# MEGA-ROS.net
KiCad netlist of a schematic drawn in EAGLE
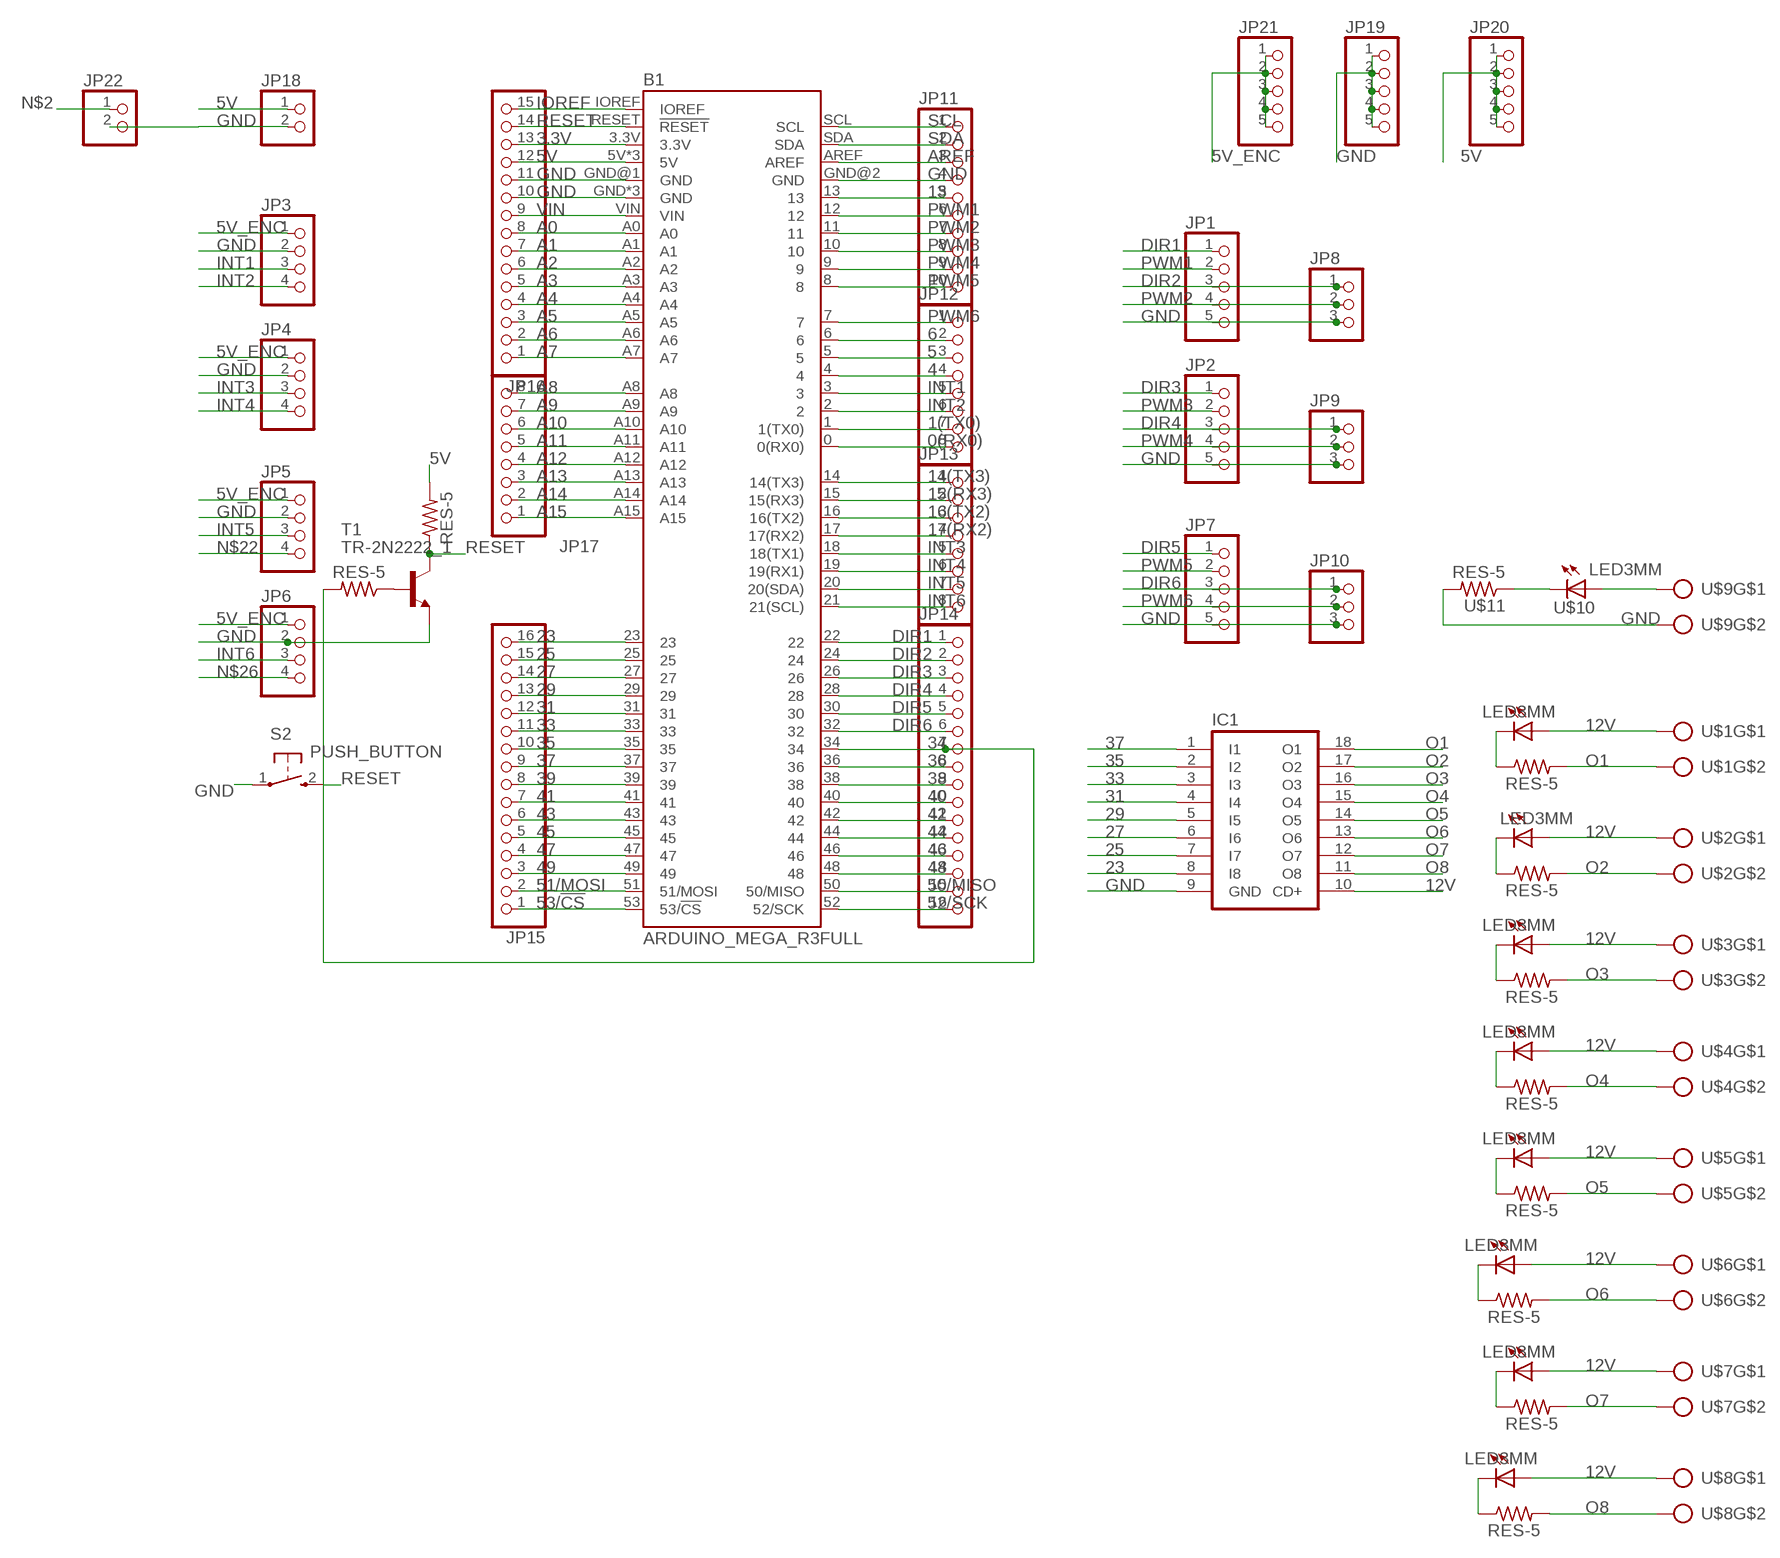
[diagram p0: schematic, sheet 1]

(export (version "E")
  (design (tool "Eeschema 10.0.6"))
  (components
    (comp (ref "B1")
      (value "ARDUINO_MEGA_R3FULL")
      (footprint "eagle-import:ARDUINO_MEGA_NO_SILK")
      (libsource (lib "eagle-import") (part "ARDUINO_MEGA_R3FULL"))
    )
    (comp (ref "IC1")
      (value "ULN2803A")
      (footprint "eagle-import:DIL18")
      (libsource (lib "eagle-import") (part "ULN2803A"))
    )
    (comp (ref "JP1")
      (value "PINHD-5_DATA")
      (footprint "eagle-import:1X05_DATA")
      (libsource (lib "eagle-import") (part "PINHD-5_DATA"))
    )
    (comp (ref "JP2")
      (value "PINHD-5_DATA")
      (footprint "eagle-import:1X05_DATA")
      (libsource (lib "eagle-import") (part "PINHD-5_DATA"))
    )
    (comp (ref "JP3")
      (value "PINHD-4_DATA")
      (footprint "eagle-import:1X04_DATA")
      (libsource (lib "eagle-import") (part "PINHD-4_DATA"))
    )
    (comp (ref "JP4")
      (value "PINHD-4_DATA")
      (footprint "eagle-import:1X04_DATA")
      (libsource (lib "eagle-import") (part "PINHD-4_DATA"))
    )
    (comp (ref "JP5")
      (value "PINHD-4_DATA")
      (footprint "eagle-import:1X04_DATA")
      (libsource (lib "eagle-import") (part "PINHD-4_DATA"))
    )
    (comp (ref "JP6")
      (value "PINHD-4_DATA")
      (footprint "eagle-import:1X04_DATA")
      (libsource (lib "eagle-import") (part "PINHD-4_DATA"))
    )
    (comp (ref "JP7")
      (value "PINHD-5_DATA")
      (footprint "eagle-import:1X05_DATA")
      (libsource (lib "eagle-import") (part "PINHD-5_DATA"))
    )
    (comp (ref "JP8")
      (value "PINHD-3_DATA")
      (footprint "eagle-import:1X03_DATA")
      (libsource (lib "eagle-import") (part "PINHD-3_DATA"))
    )
    (comp (ref "JP9")
      (value "PINHD-3_DATA")
      (footprint "eagle-import:1X03_DATA")
      (libsource (lib "eagle-import") (part "PINHD-3_DATA"))
    )
    (comp (ref "JP10")
      (value "PINHD-3_DATA")
      (footprint "eagle-import:1X03_DATA")
      (libsource (lib "eagle-import") (part "PINHD-3_DATA"))
    )
    (comp (ref "JP11")
      (value "PINHD-1X10")
      (footprint "eagle-import:1X10")
      (libsource (lib "eagle-import") (part "PINHD-1X10"))
    )
    (comp (ref "JP12")
      (value "PINHD-1X8")
      (footprint "eagle-import:1X08")
      (libsource (lib "eagle-import") (part "PINHD-1X8"))
    )
    (comp (ref "JP13")
      (value "PINHD-1X8")
      (footprint "eagle-import:1X08")
      (libsource (lib "eagle-import") (part "PINHD-1X8"))
    )
    (comp (ref "JP14")
      (value "PINHD-1X16")
      (footprint "eagle-import:1X16")
      (libsource (lib "eagle-import") (part "PINHD-1X16"))
    )
    (comp (ref "JP15")
      (value "PINHD-1X16")
      (footprint "eagle-import:1X16")
      (libsource (lib "eagle-import") (part "PINHD-1X16"))
    )
    (comp (ref "JP16")
      (value "PINHD-1X15")
      (footprint "eagle-import:1X15")
      (libsource (lib "eagle-import") (part "PINHD-1X15"))
    )
    (comp (ref "JP17")
      (value "PINHD-1X8")
      (footprint "eagle-import:1X08")
      (libsource (lib "eagle-import") (part "PINHD-1X8"))
    )
    (comp (ref "JP18")
      (value "PINHD-2_DATA")
      (footprint "eagle-import:1X02_DATA")
      (libsource (lib "eagle-import") (part "PINHD-2_DATA"))
    )
    (comp (ref "JP19")
      (value "PINHD-1X5")
      (footprint "eagle-import:1X05")
      (libsource (lib "eagle-import") (part "PINHD-1X5"))
    )
    (comp (ref "JP20")
      (value "PINHD-1X5")
      (footprint "eagle-import:1X05")
      (libsource (lib "eagle-import") (part "PINHD-1X5"))
    )
    (comp (ref "JP21")
      (value "PINHD-1X5")
      (footprint "eagle-import:1X05")
      (libsource (lib "eagle-import") (part "PINHD-1X5"))
    )
    (comp (ref "JP22")
      (value "PINHD-2_DATA")
      (footprint "eagle-import:1X02_DATA")
      (libsource (lib "eagle-import") (part "PINHD-2_DATA"))
    )
    (comp (ref "S2")
      (value "PUSH_BUTTON")
      (footprint "eagle-import:B3F-10XX")
      (libsource (lib "eagle-import") (part "PUSH_BUTTON"))
    )
    (comp (ref "T1")
      (value "TR-2N2222_1")
      (footprint "eagle-import:TO92-EBC")
      (libsource (lib "eagle-import") (part "TR-2N2222_1"))
    )
    (comp (ref "U$1")
      (value "CON_PTR_2")
      (footprint "eagle-import:AK300_2")
      (libsource (lib "eagle-import") (part "CON_PTR_2"))
    )
    (comp (ref "U$2")
      (value "CON_PTR_2")
      (footprint "eagle-import:AK300_2")
      (libsource (lib "eagle-import") (part "CON_PTR_2"))
    )
    (comp (ref "U$3")
      (value "CON_PTR_2")
      (footprint "eagle-import:AK300_2")
      (libsource (lib "eagle-import") (part "CON_PTR_2"))
    )
    (comp (ref "U$4")
      (value "CON_PTR_2")
      (footprint "eagle-import:AK300_2")
      (libsource (lib "eagle-import") (part "CON_PTR_2"))
    )
    (comp (ref "U$5")
      (value "CON_PTR_2")
      (footprint "eagle-import:AK300_2")
      (libsource (lib "eagle-import") (part "CON_PTR_2"))
    )
    (comp (ref "U$6")
      (value "CON_PTR_2")
      (footprint "eagle-import:AK300_2")
      (libsource (lib "eagle-import") (part "CON_PTR_2"))
    )
    (comp (ref "U$7")
      (value "CON_PTR_2")
      (footprint "eagle-import:AK300_2")
      (libsource (lib "eagle-import") (part "CON_PTR_2"))
    )
    (comp (ref "U$8")
      (value "CON_PTR_2")
      (footprint "eagle-import:AK300_2")
      (libsource (lib "eagle-import") (part "CON_PTR_2"))
    )
    (comp (ref "U$9")
      (value "CON_PTR_2")
      (footprint "eagle-import:AK300_2")
      (libsource (lib "eagle-import") (part "CON_PTR_2"))
    )
    (comp (ref "U$10")
      (value "LED3MM")
      (footprint "eagle-import:LED3MM")
      (libsource (lib "eagle-import") (part "LED3MM"))
    )
    (comp (ref "U$11")
      (value "RES-5")
      (footprint "eagle-import:0204_5")
      (libsource (lib "eagle-import") (part "RES-5"))
    )
    (comp (ref "U$12")
      (value "LED3MM")
      (footprint "eagle-import:LED3MM")
      (libsource (lib "eagle-import") (part "LED3MM"))
    )
    (comp (ref "U$13")
      (value "RES-5")
      (footprint "eagle-import:0204_5")
      (libsource (lib "eagle-import") (part "RES-5"))
    )
    (comp (ref "U$14")
      (value "LED3MM")
      (footprint "eagle-import:LED3MM")
      (libsource (lib "eagle-import") (part "LED3MM"))
    )
    (comp (ref "U$15")
      (value "RES-5")
      (footprint "eagle-import:0204_5")
      (libsource (lib "eagle-import") (part "RES-5"))
    )
    (comp (ref "U$16")
      (value "LED3MM")
      (footprint "eagle-import:LED3MM")
      (libsource (lib "eagle-import") (part "LED3MM"))
    )
    (comp (ref "U$17")
      (value "RES-5")
      (footprint "eagle-import:0204_5")
      (libsource (lib "eagle-import") (part "RES-5"))
    )
    (comp (ref "U$18")
      (value "LED3MM")
      (footprint "eagle-import:LED3MM")
      (libsource (lib "eagle-import") (part "LED3MM"))
    )
    (comp (ref "U$19")
      (value "RES-5")
      (footprint "eagle-import:0204_5")
      (libsource (lib "eagle-import") (part "RES-5"))
    )
    (comp (ref "U$20")
      (value "LED3MM")
      (footprint "eagle-import:LED3MM")
      (libsource (lib "eagle-import") (part "LED3MM"))
    )
    (comp (ref "U$21")
      (value "RES-5")
      (footprint "eagle-import:0204_5")
      (libsource (lib "eagle-import") (part "RES-5"))
    )
    (comp (ref "U$22")
      (value "LED3MM")
      (footprint "eagle-import:LED3MM")
      (libsource (lib "eagle-import") (part "LED3MM"))
    )
    (comp (ref "U$23")
      (value "RES-5")
      (footprint "eagle-import:0204_5")
      (libsource (lib "eagle-import") (part "RES-5"))
    )
    (comp (ref "U$24")
      (value "LED3MM")
      (footprint "eagle-import:LED3MM")
      (libsource (lib "eagle-import") (part "LED3MM"))
    )
    (comp (ref "U$25")
      (value "RES-5")
      (footprint "eagle-import:0204_5")
      (libsource (lib "eagle-import") (part "RES-5"))
    )
    (comp (ref "U$26")
      (value "LED3MM")
      (footprint "eagle-import:LED3MM")
      (libsource (lib "eagle-import") (part "LED3MM"))
    )
    (comp (ref "U$27")
      (value "RES-5")
      (footprint "eagle-import:0204_5")
      (libsource (lib "eagle-import") (part "RES-5"))
    )
    (comp (ref "U$28")
      (value "RES-5")
      (footprint "eagle-import:0204_5")
      (libsource (lib "eagle-import") (part "RES-5"))
    )
    (comp (ref "U$29")
      (value "RES-5")
      (footprint "eagle-import:0204_5")
      (libsource (lib "eagle-import") (part "RES-5"))
    )
  )
  (nets
    (net (code "1") (name "/0(RX0)") (class "Default")
      (node (ref "B1") (pin "0") (pinfunction "0(RX0)_0") (pintype "bidirectional"))
      (node (ref "JP12") (pin "8") (pinfunction "8_8") (pintype "passive"))
    )
    (net (code "2") (name "/1(TX0)") (class "Default")
      (node (ref "B1") (pin "1") (pinfunction "1(TX0)_1") (pintype "bidirectional"))
      (node (ref "JP12") (pin "7") (pinfunction "7_7") (pintype "passive"))
    )
    (net (code "3") (name "/3.3V") (class "Default")
      (node (ref "B1") (pin "3.3V") (pinfunction "3.3V_3.3V") (pintype "bidirectional"))
      (node (ref "JP16") (pin "13") (pinfunction "13_13") (pintype "passive"))
    )
    (net (code "4") (name "/4") (class "Default")
      (node (ref "B1") (pin "4") (pinfunction "4_4") (pintype "bidirectional"))
      (node (ref "JP12") (pin "4") (pinfunction "4_4") (pintype "passive"))
    )
    (net (code "5") (name "/5") (class "Default")
      (node (ref "B1") (pin "5") (pinfunction "5_5") (pintype "bidirectional"))
      (node (ref "JP12") (pin "3") (pinfunction "3_3") (pintype "passive"))
    )
    (net (code "6") (name "/5V") (class "Default")
      (node (ref "B1") (pin "5V") (pinfunction "5V_5V") (pintype "bidirectional"))
      (node (ref "B1") (pin "5V@1") (pinfunction "5V_5V@1") (pintype "bidirectional"))
      (node (ref "B1") (pin "5V@2") (pinfunction "5V_5V@2") (pintype "bidirectional"))
      (node (ref "JP16") (pin "12") (pinfunction "12_12") (pintype "passive"))
      (node (ref "JP18") (pin "1") (pinfunction "1_1") (pintype "passive"))
      (node (ref "JP20") (pin "1") (pinfunction "1_1") (pintype "passive"))
      (node (ref "JP20") (pin "2") (pinfunction "2_2") (pintype "passive"))
      (node (ref "JP20") (pin "3") (pinfunction "3_3") (pintype "passive"))
      (node (ref "JP20") (pin "4") (pinfunction "4_4") (pintype "passive"))
      (node (ref "JP20") (pin "5") (pinfunction "5_5") (pintype "passive"))
      (node (ref "U$28") (pin "2") (pinfunction "2_2") (pintype "passive"))
    )
    (net (code "7") (name "/5V_ENC") (class "Default")
      (node (ref "JP21") (pin "1") (pinfunction "1_1") (pintype "passive"))
      (node (ref "JP21") (pin "2") (pinfunction "2_2") (pintype "passive"))
      (node (ref "JP21") (pin "3") (pinfunction "3_3") (pintype "passive"))
      (node (ref "JP21") (pin "4") (pinfunction "4_4") (pintype "passive"))
      (node (ref "JP21") (pin "5") (pinfunction "5_5") (pintype "passive"))
      (node (ref "JP3") (pin "1") (pinfunction "1_1") (pintype "passive"))
      (node (ref "JP4") (pin "1") (pinfunction "1_1") (pintype "passive"))
      (node (ref "JP5") (pin "1") (pinfunction "1_1") (pintype "passive"))
      (node (ref "JP6") (pin "1") (pinfunction "1_1") (pintype "passive"))
    )
    (net (code "8") (name "/6") (class "Default")
      (node (ref "B1") (pin "6") (pinfunction "6_6") (pintype "bidirectional"))
      (node (ref "JP12") (pin "2") (pinfunction "2_2") (pintype "passive"))
    )
    (net (code "9") (name "/12V") (class "Default")
      (node (ref "IC1") (pin "10") (pinfunction "CD+_10") (pintype "passive"))
      (node (ref "U$1") (pin "1") (pinfunction "KL_1") (pintype "passive"))
      (node (ref "U$12") (pin "A") (pinfunction "A_A") (pintype "passive"))
      (node (ref "U$14") (pin "A") (pinfunction "A_A") (pintype "passive"))
      (node (ref "U$16") (pin "A") (pinfunction "A_A") (pintype "passive"))
      (node (ref "U$18") (pin "A") (pinfunction "A_A") (pintype "passive"))
      (node (ref "U$2") (pin "1") (pinfunction "KL_1") (pintype "passive"))
      (node (ref "U$20") (pin "A") (pinfunction "A_A") (pintype "passive"))
      (node (ref "U$22") (pin "A") (pinfunction "A_A") (pintype "passive"))
      (node (ref "U$24") (pin "A") (pinfunction "A_A") (pintype "passive"))
      (node (ref "U$26") (pin "A") (pinfunction "A_A") (pintype "passive"))
      (node (ref "U$3") (pin "1") (pinfunction "KL_1") (pintype "passive"))
      (node (ref "U$4") (pin "1") (pinfunction "KL_1") (pintype "passive"))
      (node (ref "U$5") (pin "1") (pinfunction "KL_1") (pintype "passive"))
      (node (ref "U$6") (pin "1") (pinfunction "KL_1") (pintype "passive"))
      (node (ref "U$7") (pin "1") (pinfunction "KL_1") (pintype "passive"))
      (node (ref "U$8") (pin "1") (pinfunction "KL_1") (pintype "passive"))
    )
    (net (code "10") (name "/13") (class "Default")
      (node (ref "B1") (pin "13") (pinfunction "13_13") (pintype "bidirectional"))
      (node (ref "JP11") (pin "5") (pinfunction "5_5") (pintype "passive"))
    )
    (net (code "11") (name "/14(TX3)") (class "Default")
      (node (ref "B1") (pin "14") (pinfunction "14(TX3)_14") (pintype "bidirectional"))
      (node (ref "JP13") (pin "1") (pinfunction "1_1") (pintype "passive"))
    )
    (net (code "12") (name "/15(RX3)") (class "Default")
      (node (ref "B1") (pin "15") (pinfunction "15(RX3)_15") (pintype "bidirectional"))
      (node (ref "JP13") (pin "2") (pinfunction "2_2") (pintype "passive"))
    )
    (net (code "13") (name "/16(TX2)") (class "Default")
      (node (ref "B1") (pin "16") (pinfunction "16(TX2)_16") (pintype "bidirectional"))
      (node (ref "JP13") (pin "3") (pinfunction "3_3") (pintype "passive"))
    )
    (net (code "14") (name "/17(RX2)") (class "Default")
      (node (ref "B1") (pin "17") (pinfunction "17(RX2)_17") (pintype "bidirectional"))
      (node (ref "JP13") (pin "4") (pinfunction "4_4") (pintype "passive"))
    )
    (net (code "15") (name "/23") (class "Default")
      (node (ref "B1") (pin "23") (pinfunction "23_23") (pintype "bidirectional"))
      (node (ref "IC1") (pin "8") (pinfunction "I8_8") (pintype "input"))
      (node (ref "JP15") (pin "16") (pinfunction "16_16") (pintype "passive"))
    )
    (net (code "16") (name "/25") (class "Default")
      (node (ref "B1") (pin "25") (pinfunction "25_25") (pintype "bidirectional"))
      (node (ref "IC1") (pin "7") (pinfunction "I7_7") (pintype "input"))
      (node (ref "JP15") (pin "15") (pinfunction "15_15") (pintype "passive"))
    )
    (net (code "17") (name "/27") (class "Default")
      (node (ref "B1") (pin "27") (pinfunction "27_27") (pintype "bidirectional"))
      (node (ref "IC1") (pin "6") (pinfunction "I6_6") (pintype "input"))
      (node (ref "JP15") (pin "14") (pinfunction "14_14") (pintype "passive"))
    )
    (net (code "18") (name "/29") (class "Default")
      (node (ref "B1") (pin "29") (pinfunction "29_29") (pintype "bidirectional"))
      (node (ref "IC1") (pin "5") (pinfunction "I5_5") (pintype "input"))
      (node (ref "JP15") (pin "13") (pinfunction "13_13") (pintype "passive"))
    )
    (net (code "19") (name "/31") (class "Default")
      (node (ref "B1") (pin "31") (pinfunction "31_31") (pintype "bidirectional"))
      (node (ref "IC1") (pin "4") (pinfunction "I4_4") (pintype "input"))
      (node (ref "JP15") (pin "12") (pinfunction "12_12") (pintype "passive"))
    )
    (net (code "20") (name "/33") (class "Default")
      (node (ref "B1") (pin "33") (pinfunction "33_33") (pintype "bidirectional"))
      (node (ref "IC1") (pin "3") (pinfunction "I3_3") (pintype "input"))
      (node (ref "JP15") (pin "11") (pinfunction "11_11") (pintype "passive"))
    )
    (net (code "21") (name "/34") (class "Default")
      (node (ref "B1") (pin "34") (pinfunction "34_34") (pintype "bidirectional"))
      (node (ref "JP14") (pin "7") (pinfunction "7_7") (pintype "passive"))
      (node (ref "U$29") (pin "2") (pinfunction "2_2") (pintype "passive"))
    )
    (net (code "22") (name "/35") (class "Default")
      (node (ref "B1") (pin "35") (pinfunction "35_35") (pintype "bidirectional"))
      (node (ref "IC1") (pin "2") (pinfunction "I2_2") (pintype "input"))
      (node (ref "JP15") (pin "10") (pinfunction "10_10") (pintype "passive"))
    )
    (net (code "23") (name "/36") (class "Default")
      (node (ref "B1") (pin "36") (pinfunction "36_36") (pintype "bidirectional"))
      (node (ref "JP14") (pin "8") (pinfunction "8_8") (pintype "passive"))
    )
    (net (code "24") (name "/37") (class "Default")
      (node (ref "B1") (pin "37") (pinfunction "37_37") (pintype "bidirectional"))
      (node (ref "IC1") (pin "1") (pinfunction "I1_1") (pintype "input"))
      (node (ref "JP15") (pin "9") (pinfunction "9_9") (pintype "passive"))
    )
    (net (code "25") (name "/38") (class "Default")
      (node (ref "B1") (pin "38") (pinfunction "38_38") (pintype "bidirectional"))
      (node (ref "JP14") (pin "9") (pinfunction "9_9") (pintype "passive"))
    )
    (net (code "26") (name "/39") (class "Default")
      (node (ref "B1") (pin "39") (pinfunction "39_39") (pintype "bidirectional"))
      (node (ref "JP15") (pin "8") (pinfunction "8_8") (pintype "passive"))
    )
    (net (code "27") (name "/40") (class "Default")
      (node (ref "B1") (pin "40") (pinfunction "40_40") (pintype "bidirectional"))
      (node (ref "JP14") (pin "10") (pinfunction "10_10") (pintype "passive"))
    )
    (net (code "28") (name "/41") (class "Default")
      (node (ref "B1") (pin "41") (pinfunction "41_41") (pintype "bidirectional"))
      (node (ref "JP15") (pin "7") (pinfunction "7_7") (pintype "passive"))
    )
    (net (code "29") (name "/42") (class "Default")
      (node (ref "B1") (pin "42") (pinfunction "42_42") (pintype "bidirectional"))
      (node (ref "JP14") (pin "11") (pinfunction "11_11") (pintype "passive"))
    )
    (net (code "30") (name "/43") (class "Default")
      (node (ref "B1") (pin "43") (pinfunction "43_43") (pintype "bidirectional"))
      (node (ref "JP15") (pin "6") (pinfunction "6_6") (pintype "passive"))
    )
    (net (code "31") (name "/44") (class "Default")
      (node (ref "B1") (pin "44") (pinfunction "44_44") (pintype "bidirectional"))
      (node (ref "JP14") (pin "12") (pinfunction "12_12") (pintype "passive"))
    )
    (net (code "32") (name "/45") (class "Default")
      (node (ref "B1") (pin "45") (pinfunction "45_45") (pintype "bidirectional"))
      (node (ref "JP15") (pin "5") (pinfunction "5_5") (pintype "passive"))
    )
    (net (code "33") (name "/46") (class "Default")
      (node (ref "B1") (pin "46") (pinfunction "46_46") (pintype "bidirectional"))
      (node (ref "JP14") (pin "13") (pinfunction "13_13") (pintype "passive"))
    )
    (net (code "34") (name "/47") (class "Default")
      (node (ref "B1") (pin "47") (pinfunction "47_47") (pintype "bidirectional"))
      (node (ref "JP15") (pin "4") (pinfunction "4_4") (pintype "passive"))
    )
    (net (code "35") (name "/48") (class "Default")
      (node (ref "B1") (pin "48") (pinfunction "48_48") (pintype "bidirectional"))
      (node (ref "JP14") (pin "14") (pinfunction "14_14") (pintype "passive"))
    )
    (net (code "36") (name "/49") (class "Default")
      (node (ref "B1") (pin "49") (pinfunction "49_49") (pintype "bidirectional"))
      (node (ref "JP15") (pin "3") (pinfunction "3_3") (pintype "passive"))
    )
    (net (code "37") (name "/50{slash}MISO") (class "Default")
      (node (ref "B1") (pin "50") (pinfunction "50/MISO_50") (pintype "bidirectional"))
      (node (ref "JP14") (pin "15") (pinfunction "15_15") (pintype "passive"))
    )
    (net (code "38") (name "/51{slash}MOSI") (class "Default")
      (node (ref "B1") (pin "51") (pinfunction "51/MOSI_51") (pintype "bidirectional"))
      (node (ref "JP15") (pin "2") (pinfunction "2_2") (pintype "passive"))
    )
    (net (code "39") (name "/52{slash}SCK") (class "Default")
      (node (ref "B1") (pin "52") (pinfunction "52/SCK_52") (pintype "bidirectional"))
      (node (ref "JP14") (pin "16") (pinfunction "16_16") (pintype "passive"))
    )
    (net (code "40") (name "/53{slash}~{CS}") (class "Default")
      (node (ref "B1") (pin "53") (pinfunction "53/~{CS}_53") (pintype "bidirectional"))
      (node (ref "JP15") (pin "1") (pinfunction "1_1") (pintype "passive"))
    )
    (net (code "41") (name "/A0") (class "Default")
      (node (ref "B1") (pin "A0") (pinfunction "A0_A0") (pintype "bidirectional"))
      (node (ref "JP16") (pin "8") (pinfunction "8_8") (pintype "passive"))
    )
    (net (code "42") (name "/A1") (class "Default")
      (node (ref "B1") (pin "A1") (pinfunction "A1_A1") (pintype "bidirectional"))
      (node (ref "JP16") (pin "7") (pinfunction "7_7") (pintype "passive"))
    )
    (net (code "43") (name "/A2") (class "Default")
      (node (ref "B1") (pin "A2") (pinfunction "A2_A2") (pintype "bidirectional"))
      (node (ref "JP16") (pin "6") (pinfunction "6_6") (pintype "passive"))
    )
    (net (code "44") (name "/A3") (class "Default")
      (node (ref "B1") (pin "A3") (pinfunction "A3_A3") (pintype "bidirectional"))
      (node (ref "JP16") (pin "5") (pinfunction "5_5") (pintype "passive"))
    )
    (net (code "45") (name "/A4") (class "Default")
      (node (ref "B1") (pin "A4") (pinfunction "A4_A4") (pintype "bidirectional"))
      (node (ref "JP16") (pin "4") (pinfunction "4_4") (pintype "passive"))
    )
    (net (code "46") (name "/A5") (class "Default")
      (node (ref "B1") (pin "A5") (pinfunction "A5_A5") (pintype "bidirectional"))
      (node (ref "JP16") (pin "3") (pinfunction "3_3") (pintype "passive"))
    )
    (net (code "47") (name "/A6") (class "Default")
      (node (ref "B1") (pin "A6") (pinfunction "A6_A6") (pintype "bidirectional"))
      (node (ref "JP16") (pin "2") (pinfunction "2_2") (pintype "passive"))
    )
    (net (code "48") (name "/A7") (class "Default")
      (node (ref "B1") (pin "A7") (pinfunction "A7_A7") (pintype "bidirectional"))
      (node (ref "JP16") (pin "1") (pinfunction "1_1") (pintype "passive"))
    )
    (net (code "49") (name "/A8") (class "Default")
      (node (ref "B1") (pin "A8") (pinfunction "A8_A8") (pintype "bidirectional"))
      (node (ref "JP17") (pin "8") (pinfunction "8_8") (pintype "passive"))
    )
    (net (code "50") (name "/A9") (class "Default")
      (node (ref "B1") (pin "A9") (pinfunction "A9_A9") (pintype "bidirectional"))
      (node (ref "JP17") (pin "7") (pinfunction "7_7") (pintype "passive"))
    )
    (net (code "51") (name "/A10") (class "Default")
      (node (ref "B1") (pin "A10") (pinfunction "A10_A10") (pintype "bidirectional"))
      (node (ref "JP17") (pin "6") (pinfunction "6_6") (pintype "passive"))
    )
    (net (code "52") (name "/A11") (class "Default")
      (node (ref "B1") (pin "A11") (pinfunction "A11_A11") (pintype "bidirectional"))
      (node (ref "JP17") (pin "5") (pinfunction "5_5") (pintype "passive"))
    )
    (net (code "53") (name "/A12") (class "Default")
      (node (ref "B1") (pin "A12") (pinfunction "A12_A12") (pintype "bidirectional"))
      (node (ref "JP17") (pin "4") (pinfunction "4_4") (pintype "passive"))
    )
    (net (code "54") (name "/A13") (class "Default")
      (node (ref "B1") (pin "A13") (pinfunction "A13_A13") (pintype "bidirectional"))
      (node (ref "JP17") (pin "3") (pinfunction "3_3") (pintype "passive"))
    )
    (net (code "55") (name "/A14") (class "Default")
      (node (ref "B1") (pin "A14") (pinfunction "A14_A14") (pintype "bidirectional"))
      (node (ref "JP17") (pin "2") (pinfunction "2_2") (pintype "passive"))
    )
    (net (code "56") (name "/A15") (class "Default")
      (node (ref "B1") (pin "A15") (pinfunction "A15_A15") (pintype "bidirectional"))
      (node (ref "JP17") (pin "1") (pinfunction "1_1") (pintype "passive"))
    )
    (net (code "57") (name "/AREF") (class "Default")
      (node (ref "B1") (pin "AREF") (pinfunction "AREF_AREF") (pintype "bidirectional"))
      (node (ref "JP11") (pin "3") (pinfunction "3_3") (pintype "passive"))
    )
    (net (code "58") (name "/DIR1") (class "Default")
      (node (ref "B1") (pin "22") (pinfunction "22_22") (pintype "bidirectional"))
      (node (ref "JP1") (pin "1") (pinfunction "1_1") (pintype "passive"))
      (node (ref "JP14") (pin "1") (pinfunction "1_1") (pintype "passive"))
    )
    (net (code "59") (name "/DIR2") (class "Default")
      (node (ref "B1") (pin "24") (pinfunction "24_24") (pintype "bidirectional"))
      (node (ref "JP1") (pin "3") (pinfunction "3_3") (pintype "passive"))
      (node (ref "JP14") (pin "2") (pinfunction "2_2") (pintype "passive"))
      (node (ref "JP8") (pin "1") (pinfunction "1_1") (pintype "passive"))
    )
    (net (code "60") (name "/DIR3") (class "Default")
      (node (ref "B1") (pin "26") (pinfunction "26_26") (pintype "bidirectional"))
      (node (ref "JP14") (pin "3") (pinfunction "3_3") (pintype "passive"))
      (node (ref "JP2") (pin "1") (pinfunction "1_1") (pintype "passive"))
    )
    (net (code "61") (name "/DIR4") (class "Default")
      (node (ref "B1") (pin "28") (pinfunction "28_28") (pintype "bidirectional"))
      (node (ref "JP14") (pin "4") (pinfunction "4_4") (pintype "passive"))
      (node (ref "JP2") (pin "3") (pinfunction "3_3") (pintype "passive"))
      (node (ref "JP9") (pin "1") (pinfunction "1_1") (pintype "passive"))
    )
    (net (code "62") (name "/DIR5") (class "Default")
      (node (ref "B1") (pin "30") (pinfunction "30_30") (pintype "bidirectional"))
      (node (ref "JP14") (pin "5") (pinfunction "5_5") (pintype "passive"))
      (node (ref "JP7") (pin "1") (pinfunction "1_1") (pintype "passive"))
    )
    (net (code "63") (name "/DIR6") (class "Default")
      (node (ref "B1") (pin "32") (pinfunction "32_32") (pintype "bidirectional"))
      (node (ref "JP10") (pin "1") (pinfunction "1_1") (pintype "passive"))
      (node (ref "JP14") (pin "6") (pinfunction "6_6") (pintype "passive"))
      (node (ref "JP7") (pin "3") (pinfunction "3_3") (pintype "passive"))
    )
    (net (code "64") (name "/GND") (class "Default")
      (node (ref "B1") (pin "GND") (pinfunction "GND_GND") (pintype "bidirectional"))
      (node (ref "B1") (pin "GND@1") (pinfunction "GND_GND@1") (pintype "bidirectional"))
      (node (ref "B1") (pin "GND@2") (pinfunction "GND_GND@2") (pintype "bidirectional"))
      (node (ref "B1") (pin "GND@3") (pinfunction "GND_GND@3") (pintype "bidirectional"))
      (node (ref "B1") (pin "GND@4") (pinfunction "GND_GND@4") (pintype "bidirectional"))
      (node (ref "IC1") (pin "9") (pinfunction "GND_9") (pintype "power_in"))
      (node (ref "JP1") (pin "5") (pinfunction "5_5") (pintype "passive"))
      (node (ref "JP10") (pin "3") (pinfunction "3_3") (pintype "passive"))
      (node (ref "JP11") (pin "4") (pinfunction "4_4") (pintype "passive"))
      (node (ref "JP16") (pin "10") (pinfunction "10_10") (pintype "passive"))
      (node (ref "JP16") (pin "11") (pinfunction "11_11") (pintype "passive"))
      (node (ref "JP18") (pin "2") (pinfunction "2_2") (pintype "passive"))
      (node (ref "JP19") (pin "1") (pinfunction "1_1") (pintype "passive"))
      (node (ref "JP19") (pin "2") (pinfunction "2_2") (pintype "passive"))
      (node (ref "JP19") (pin "3") (pinfunction "3_3") (pintype "passive"))
      (node (ref "JP19") (pin "4") (pinfunction "4_4") (pintype "passive"))
      (node (ref "JP19") (pin "5") (pinfunction "5_5") (pintype "passive"))
      (node (ref "JP2") (pin "5") (pinfunction "5_5") (pintype "passive"))
      (node (ref "JP22") (pin "2") (pinfunction "2_2") (pintype "passive"))
      (node (ref "JP3") (pin "2") (pinfunction "2_2") (pintype "passive"))
      (node (ref "JP4") (pin "2") (pinfunction "2_2") (pintype "passive"))
      (node (ref "JP5") (pin "2") (pinfunction "2_2") (pintype "passive"))
      (node (ref "JP6") (pin "2") (pinfunction "2_2") (pintype "passive"))
      (node (ref "JP7") (pin "5") (pinfunction "5_5") (pintype "passive"))
      (node (ref "JP8") (pin "3") (pinfunction "3_3") (pintype "passive"))
      (node (ref "JP9") (pin "3") (pinfunction "3_3") (pintype "passive"))
      (node (ref "S2") (pin "1") (pinfunction "P_1") (pintype "passive"))
      (node (ref "T1") (pin "E") (pinfunction "E_E") (pintype "passive"))
      (node (ref "U$11") (pin "2") (pinfunction "2_2") (pintype "passive"))
      (node (ref "U$9") (pin "2") (pinfunction "KL_2") (pintype "passive"))
    )
    (net (code "65") (name "/INT1") (class "Default")
      (node (ref "B1") (pin "3") (pinfunction "3_3") (pintype "bidirectional"))
      (node (ref "JP12") (pin "5") (pinfunction "5_5") (pintype "passive"))
      (node (ref "JP3") (pin "3") (pinfunction "3_3") (pintype "passive"))
    )
    (net (code "66") (name "/INT2") (class "Default")
      (node (ref "B1") (pin "2") (pinfunction "2_2") (pintype "bidirectional"))
      (node (ref "JP12") (pin "6") (pinfunction "6_6") (pintype "passive"))
      (node (ref "JP3") (pin "4") (pinfunction "4_4") (pintype "passive"))
    )
    (net (code "67") (name "/INT3") (class "Default")
      (node (ref "B1") (pin "18") (pinfunction "18(TX1)_18") (pintype "bidirectional"))
      (node (ref "JP13") (pin "5") (pinfunction "5_5") (pintype "passive"))
      (node (ref "JP4") (pin "3") (pinfunction "3_3") (pintype "passive"))
    )
    (net (code "68") (name "/INT4") (class "Default")
      (node (ref "B1") (pin "19") (pinfunction "19(RX1)_19") (pintype "bidirectional"))
      (node (ref "JP13") (pin "6") (pinfunction "6_6") (pintype "passive"))
      (node (ref "JP4") (pin "4") (pinfunction "4_4") (pintype "passive"))
    )
    (net (code "69") (name "/INT5") (class "Default")
      (node (ref "B1") (pin "20") (pinfunction "20(SDA)_20") (pintype "bidirectional"))
      (node (ref "JP13") (pin "7") (pinfunction "7_7") (pintype "passive"))
      (node (ref "JP5") (pin "3") (pinfunction "3_3") (pintype "passive"))
    )
    (net (code "70") (name "/INT6") (class "Default")
      (node (ref "B1") (pin "21") (pinfunction "21(SCL)_21") (pintype "bidirectional"))
      (node (ref "JP13") (pin "8") (pinfunction "8_8") (pintype "passive"))
      (node (ref "JP6") (pin "3") (pinfunction "3_3") (pintype "passive"))
    )
    (net (code "71") (name "/IOREF") (class "Default")
      (node (ref "B1") (pin "IOREF") (pinfunction "IOREF_IOREF") (pintype "bidirectional"))
      (node (ref "JP16") (pin "15") (pinfunction "15_15") (pintype "passive"))
    )
    (net (code "72") (name "/N$2") (class "Default")
      (node (ref "JP22") (pin "1") (pinfunction "1_1") (pintype "passive"))
    )
    (net (code "73") (name "/N$22") (class "Default")
      (node (ref "JP5") (pin "4") (pinfunction "4_4") (pintype "passive"))
    )
    (net (code "74") (name "/N$26") (class "Default")
      (node (ref "JP6") (pin "4") (pinfunction "4_4") (pintype "passive"))
    )
    (net (code "75") (name "/O1") (class "Default")
      (node (ref "IC1") (pin "18") (pinfunction "O1_18") (pintype "open_collector"))
      (node (ref "U$1") (pin "2") (pinfunction "KL_2") (pintype "passive"))
      (node (ref "U$13") (pin "2") (pinfunction "2_2") (pintype "passive"))
    )
    (net (code "76") (name "/O2") (class "Default")
      (node (ref "IC1") (pin "17") (pinfunction "O2_17") (pintype "open_collector"))
      (node (ref "U$15") (pin "2") (pinfunction "2_2") (pintype "passive"))
      (node (ref "U$2") (pin "2") (pinfunction "KL_2") (pintype "passive"))
    )
    (net (code "77") (name "/O3") (class "Default")
      (node (ref "IC1") (pin "16") (pinfunction "O3_16") (pintype "open_collector"))
      (node (ref "U$17") (pin "2") (pinfunction "2_2") (pintype "passive"))
      (node (ref "U$3") (pin "2") (pinfunction "KL_2") (pintype "passive"))
    )
    (net (code "78") (name "/O4") (class "Default")
      (node (ref "IC1") (pin "15") (pinfunction "O4_15") (pintype "open_collector"))
      (node (ref "U$19") (pin "2") (pinfunction "2_2") (pintype "passive"))
      (node (ref "U$4") (pin "2") (pinfunction "KL_2") (pintype "passive"))
    )
    (net (code "79") (name "/O5") (class "Default")
      (node (ref "IC1") (pin "14") (pinfunction "O5_14") (pintype "open_collector"))
      (node (ref "U$21") (pin "2") (pinfunction "2_2") (pintype "passive"))
      (node (ref "U$5") (pin "2") (pinfunction "KL_2") (pintype "passive"))
    )
    (net (code "80") (name "/O6") (class "Default")
      (node (ref "IC1") (pin "13") (pinfunction "O6_13") (pintype "open_collector"))
      (node (ref "U$23") (pin "2") (pinfunction "2_2") (pintype "passive"))
      (node (ref "U$6") (pin "2") (pinfunction "KL_2") (pintype "passive"))
    )
    (net (code "81") (name "/O7") (class "Default")
      (node (ref "IC1") (pin "12") (pinfunction "O7_12") (pintype "open_collector"))
      (node (ref "U$25") (pin "2") (pinfunction "2_2") (pintype "passive"))
      (node (ref "U$7") (pin "2") (pinfunction "KL_2") (pintype "passive"))
    )
    (net (code "82") (name "/O8") (class "Default")
      (node (ref "IC1") (pin "11") (pinfunction "O8_11") (pintype "open_collector"))
      (node (ref "U$27") (pin "2") (pinfunction "2_2") (pintype "passive"))
      (node (ref "U$8") (pin "2") (pinfunction "KL_2") (pintype "passive"))
    )
    (net (code "83") (name "/PWM1") (class "Default")
      (node (ref "B1") (pin "12") (pinfunction "12_12") (pintype "bidirectional"))
      (node (ref "JP1") (pin "2") (pinfunction "2_2") (pintype "passive"))
      (node (ref "JP11") (pin "6") (pinfunction "6_6") (pintype "passive"))
    )
    (net (code "84") (name "/PWM2") (class "Default")
      (node (ref "B1") (pin "11") (pinfunction "11_11") (pintype "bidirectional"))
      (node (ref "JP1") (pin "4") (pinfunction "4_4") (pintype "passive"))
      (node (ref "JP11") (pin "7") (pinfunction "7_7") (pintype "passive"))
      (node (ref "JP8") (pin "2") (pinfunction "2_2") (pintype "passive"))
    )
    (net (code "85") (name "/PWM3") (class "Default")
      (node (ref "B1") (pin "10") (pinfunction "10_10") (pintype "bidirectional"))
      (node (ref "JP11") (pin "8") (pinfunction "8_8") (pintype "passive"))
      (node (ref "JP2") (pin "2") (pinfunction "2_2") (pintype "passive"))
    )
    (net (code "86") (name "/PWM4") (class "Default")
      (node (ref "B1") (pin "9") (pinfunction "9_9") (pintype "bidirectional"))
      (node (ref "JP11") (pin "9") (pinfunction "9_9") (pintype "passive"))
      (node (ref "JP2") (pin "4") (pinfunction "4_4") (pintype "passive"))
      (node (ref "JP9") (pin "2") (pinfunction "2_2") (pintype "passive"))
    )
    (net (code "87") (name "/PWM5") (class "Default")
      (node (ref "B1") (pin "8") (pinfunction "8_8") (pintype "bidirectional"))
      (node (ref "JP11") (pin "10") (pinfunction "10_10") (pintype "passive"))
      (node (ref "JP7") (pin "2") (pinfunction "2_2") (pintype "passive"))
    )
    (net (code "88") (name "/PWM6") (class "Default")
      (node (ref "B1") (pin "7") (pinfunction "7_7") (pintype "bidirectional"))
      (node (ref "JP10") (pin "2") (pinfunction "2_2") (pintype "passive"))
      (node (ref "JP12") (pin "1") (pinfunction "1_1") (pintype "passive"))
      (node (ref "JP7") (pin "4") (pinfunction "4_4") (pintype "passive"))
    )
    (net (code "89") (name "/RESET") (class "Default")
      (node (ref "B1") (pin "RESET") (pinfunction "~{RESET}_RESET") (pintype "bidirectional"))
      (node (ref "JP16") (pin "14") (pinfunction "14_14") (pintype "passive"))
      (node (ref "S2") (pin "2") (pinfunction "S_2") (pintype "passive"))
      (node (ref "T1") (pin "C") (pinfunction "C_C") (pintype "passive"))
      (node (ref "U$28") (pin "1") (pinfunction "1_1") (pintype "passive"))
    )
    (net (code "90") (name "/SCL") (class "Default")
      (node (ref "B1") (pin "SCL") (pinfunction "SCL_SCL") (pintype "bidirectional"))
      (node (ref "JP11") (pin "1") (pinfunction "1_1") (pintype "passive"))
    )
    (net (code "91") (name "/SDA") (class "Default")
      (node (ref "B1") (pin "SDA") (pinfunction "SDA_SDA") (pintype "bidirectional"))
      (node (ref "JP11") (pin "2") (pinfunction "2_2") (pintype "passive"))
    )
    (net (code "92") (name "/VIN") (class "Default")
      (node (ref "B1") (pin "VIN") (pinfunction "VIN_VIN") (pintype "bidirectional"))
      (node (ref "JP16") (pin "9") (pinfunction "9_9") (pintype "passive"))
    )
    (net (code "93") (name "Net-(T1-PadB)") (class "Default")
      (node (ref "T1") (pin "B") (pinfunction "B_B") (pintype "passive"))
      (node (ref "U$29") (pin "1") (pinfunction "1_1") (pintype "passive"))
    )
    (net (code "94") (name "Net-(U$9A-KL)") (class "Default")
      (node (ref "U$10") (pin "A") (pinfunction "A_A") (pintype "passive"))
      (node (ref "U$9") (pin "1") (pinfunction "KL_1") (pintype "passive"))
    )
    (net (code "95") (name "Net-(U$10-C)") (class "Default")
      (node (ref "U$10") (pin "K") (pinfunction "C_K") (pintype "passive"))
      (node (ref "U$11") (pin "1") (pinfunction "1_1") (pintype "passive"))
    )
    (net (code "96") (name "Net-(U$12-C)") (class "Default")
      (node (ref "U$12") (pin "K") (pinfunction "C_K") (pintype "passive"))
      (node (ref "U$13") (pin "1") (pinfunction "1_1") (pintype "passive"))
    )
    (net (code "97") (name "Net-(U$14-C)") (class "Default")
      (node (ref "U$14") (pin "K") (pinfunction "C_K") (pintype "passive"))
      (node (ref "U$15") (pin "1") (pinfunction "1_1") (pintype "passive"))
    )
    (net (code "98") (name "Net-(U$16-C)") (class "Default")
      (node (ref "U$16") (pin "K") (pinfunction "C_K") (pintype "passive"))
      (node (ref "U$17") (pin "1") (pinfunction "1_1") (pintype "passive"))
    )
    (net (code "99") (name "Net-(U$18-C)") (class "Default")
      (node (ref "U$18") (pin "K") (pinfunction "C_K") (pintype "passive"))
      (node (ref "U$19") (pin "1") (pinfunction "1_1") (pintype "passive"))
    )
    (net (code "100") (name "Net-(U$20-C)") (class "Default")
      (node (ref "U$20") (pin "K") (pinfunction "C_K") (pintype "passive"))
      (node (ref "U$21") (pin "1") (pinfunction "1_1") (pintype "passive"))
    )
    (net (code "101") (name "Net-(U$22-C)") (class "Default")
      (node (ref "U$22") (pin "K") (pinfunction "C_K") (pintype "passive"))
      (node (ref "U$23") (pin "1") (pinfunction "1_1") (pintype "passive"))
    )
    (net (code "102") (name "Net-(U$24-C)") (class "Default")
      (node (ref "U$24") (pin "K") (pinfunction "C_K") (pintype "passive"))
      (node (ref "U$25") (pin "1") (pinfunction "1_1") (pintype "passive"))
    )
    (net (code "103") (name "Net-(U$26-C)") (class "Default")
      (node (ref "U$26") (pin "K") (pinfunction "C_K") (pintype "passive"))
      (node (ref "U$27") (pin "1") (pinfunction "1_1") (pintype "passive"))
    )
  )
)
